# uv-dosimeter-guva-op-amp-mk-1_3.net
KiCad netlist of a schematic drawn in EAGLE
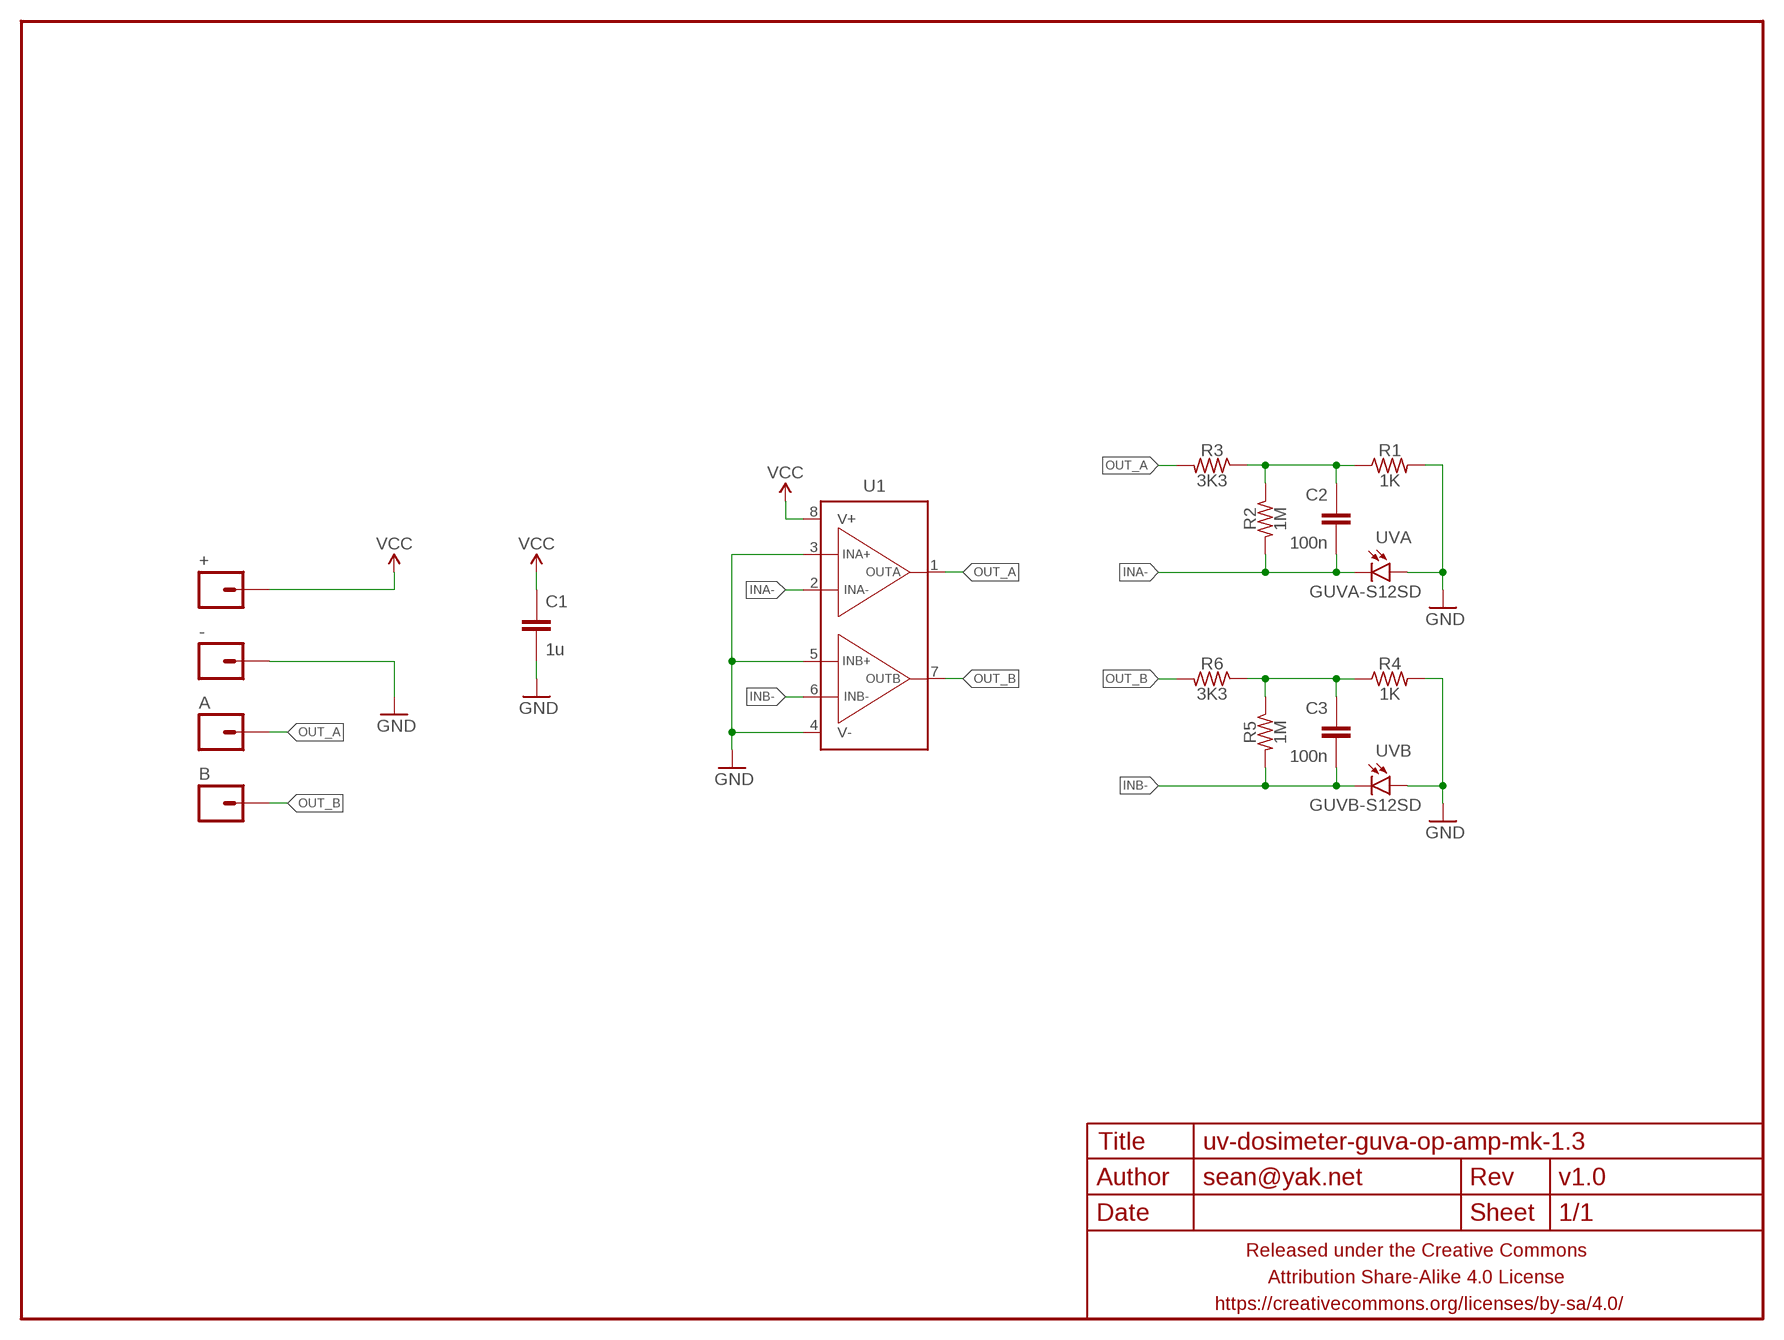
[diagram p0: schematic, sheet 1]

(export (version "E")
  (design (tool "Eeschema 10.0.6"))
  (components
    (comp (ref "+")
      (value "M01PTH")
      (footprint "eagle-import:1X01")
      (libsource (lib "eagle-import") (part "M01PTH"))
    )
    (comp (ref "-")
      (value "M01PTH")
      (footprint "eagle-import:1X01")
      (libsource (lib "eagle-import") (part "M01PTH"))
    )
    (comp (ref "A")
      (value "M01PTH")
      (footprint "eagle-import:1X01")
      (libsource (lib "eagle-import") (part "M01PTH"))
    )
    (comp (ref "B")
      (value "M01PTH")
      (footprint "eagle-import:1X01")
      (libsource (lib "eagle-import") (part "M01PTH"))
    )
    (comp (ref "C1")
      (value "1u")
      (footprint "eagle-import:C0603")
      (libsource (lib "eagle-import") (part "CAPACITOR-CERAMICC0603"))
    )
    (comp (ref "C2")
      (value "100n")
      (footprint "eagle-import:C0603")
      (libsource (lib "eagle-import") (part "CAPACITOR-CERAMICC0603"))
    )
    (comp (ref "C3")
      (value "100n")
      (footprint "eagle-import:C0603")
      (libsource (lib "eagle-import") (part "CAPACITOR-CERAMICC0603"))
    )
    (comp (ref "FRAME1")
      (value "FRAME-LETTERNO_PACKAGE")
      (footprint "eagle-import:DUMMY")
      (fields (field (name "DESIGNER") "sean@yak.net") (field (name "VERSION") "v1.0"))
      (libsource (lib "eagle-import") (part "FRAME-LETTERNO_PACKAGE"))
    )
    (comp (ref "R1")
      (value "1K")
      (footprint "eagle-import:R0603")
      (libsource (lib "eagle-import") (part "RESISTORR0603"))
    )
    (comp (ref "R2")
      (value "1M")
      (footprint "eagle-import:R0603")
      (libsource (lib "eagle-import") (part "RESISTORR0603"))
    )
    (comp (ref "R3")
      (value "3K3")
      (footprint "eagle-import:R0603")
      (libsource (lib "eagle-import") (part "RESISTORR0603"))
    )
    (comp (ref "R4")
      (value "1K")
      (footprint "eagle-import:R0603")
      (libsource (lib "eagle-import") (part "RESISTORR0603"))
    )
    (comp (ref "R5")
      (value "1M")
      (footprint "eagle-import:R0603")
      (libsource (lib "eagle-import") (part "RESISTORR0603"))
    )
    (comp (ref "R6")
      (value "3K3")
      (footprint "eagle-import:R0603")
      (libsource (lib "eagle-import") (part "RESISTORR0603"))
    )
    (comp (ref "U1")
      (value "MCP6002MSOP")
      (footprint "eagle-import:MSOP-8")
      (libsource (lib "eagle-import") (part "MCP6002MSOP"))
    )
    (comp (ref "UVA")
      (value "GUVA-S12SD")
      (footprint "eagle-import:LED3528")
      (libsource (lib "eagle-import") (part "GUVA-S12SDLED3528"))
    )
    (comp (ref "UVB")
      (value "GUVB-S12SD")
      (footprint "eagle-import:LED3528")
      (libsource (lib "eagle-import") (part "GUVA-S12SDLED3528"))
    )
  )
  (nets
    (net (code "1") (name "GND") (class "Default")
      (node (ref "-") (pin "1") (pinfunction "1_1") (pintype "passive"))
      (node (ref "C1") (pin "2") (pinfunction "2_2") (pintype "passive"))
      (node (ref "R1") (pin "2") (pinfunction "2_2") (pintype "passive"))
      (node (ref "R4") (pin "2") (pinfunction "2_2") (pintype "passive"))
      (node (ref "U1") (pin "3") (pinfunction "INA+_3") (pintype "input"))
      (node (ref "U1") (pin "4") (pinfunction "V-_4") (pintype "power_in"))
      (node (ref "U1") (pin "5") (pinfunction "INB+_5") (pintype "input"))
      (node (ref "UVA") (pin "A") (pinfunction "A_A") (pintype "passive"))
      (node (ref "UVB") (pin "A") (pinfunction "A_A") (pintype "passive"))
    )
    (net (code "2") (name "INA-") (class "Default")
      (node (ref "C2") (pin "2") (pinfunction "2_2") (pintype "passive"))
      (node (ref "R2") (pin "2") (pinfunction "2_2") (pintype "passive"))
      (node (ref "U1") (pin "2") (pinfunction "INA-_2") (pintype "input"))
      (node (ref "UVA") (pin "K") (pinfunction "C_K") (pintype "passive"))
    )
    (net (code "3") (name "INB-") (class "Default")
      (node (ref "C3") (pin "2") (pinfunction "2_2") (pintype "passive"))
      (node (ref "R5") (pin "2") (pinfunction "2_2") (pintype "passive"))
      (node (ref "U1") (pin "6") (pinfunction "INB-_6") (pintype "input"))
      (node (ref "UVB") (pin "K") (pinfunction "C_K") (pintype "passive"))
    )
    (net (code "4") (name "Net-(C2-Pad1)") (class "Default")
      (node (ref "C2") (pin "1") (pinfunction "1_1") (pintype "passive"))
      (node (ref "R1") (pin "1") (pinfunction "1_1") (pintype "passive"))
      (node (ref "R2") (pin "1") (pinfunction "1_1") (pintype "passive"))
      (node (ref "R3") (pin "1") (pinfunction "1_1") (pintype "passive"))
    )
    (net (code "5") (name "Net-(C3-Pad1)") (class "Default")
      (node (ref "C3") (pin "1") (pinfunction "1_1") (pintype "passive"))
      (node (ref "R4") (pin "1") (pinfunction "1_1") (pintype "passive"))
      (node (ref "R5") (pin "1") (pinfunction "1_1") (pintype "passive"))
      (node (ref "R6") (pin "1") (pinfunction "1_1") (pintype "passive"))
    )
    (net (code "6") (name "OUT_A") (class "Default")
      (node (ref "A") (pin "1") (pinfunction "1_1") (pintype "passive"))
      (node (ref "R3") (pin "2") (pinfunction "2_2") (pintype "passive"))
      (node (ref "U1") (pin "1") (pinfunction "OUTA_1") (pintype "output"))
    )
    (net (code "7") (name "OUT_B") (class "Default")
      (node (ref "B") (pin "1") (pinfunction "1_1") (pintype "passive"))
      (node (ref "R6") (pin "2") (pinfunction "2_2") (pintype "passive"))
      (node (ref "U1") (pin "7") (pinfunction "OUTB_7") (pintype "output"))
    )
    (net (code "8") (name "VCC") (class "Default")
      (node (ref "+") (pin "1") (pinfunction "1_1") (pintype "passive"))
      (node (ref "C1") (pin "1") (pinfunction "1_1") (pintype "passive"))
      (node (ref "U1") (pin "8") (pinfunction "V+_8") (pintype "power_in"))
    )
  )
)
